# MD015A.net
KiCad netlist of a schematic drawn in Altium Designer
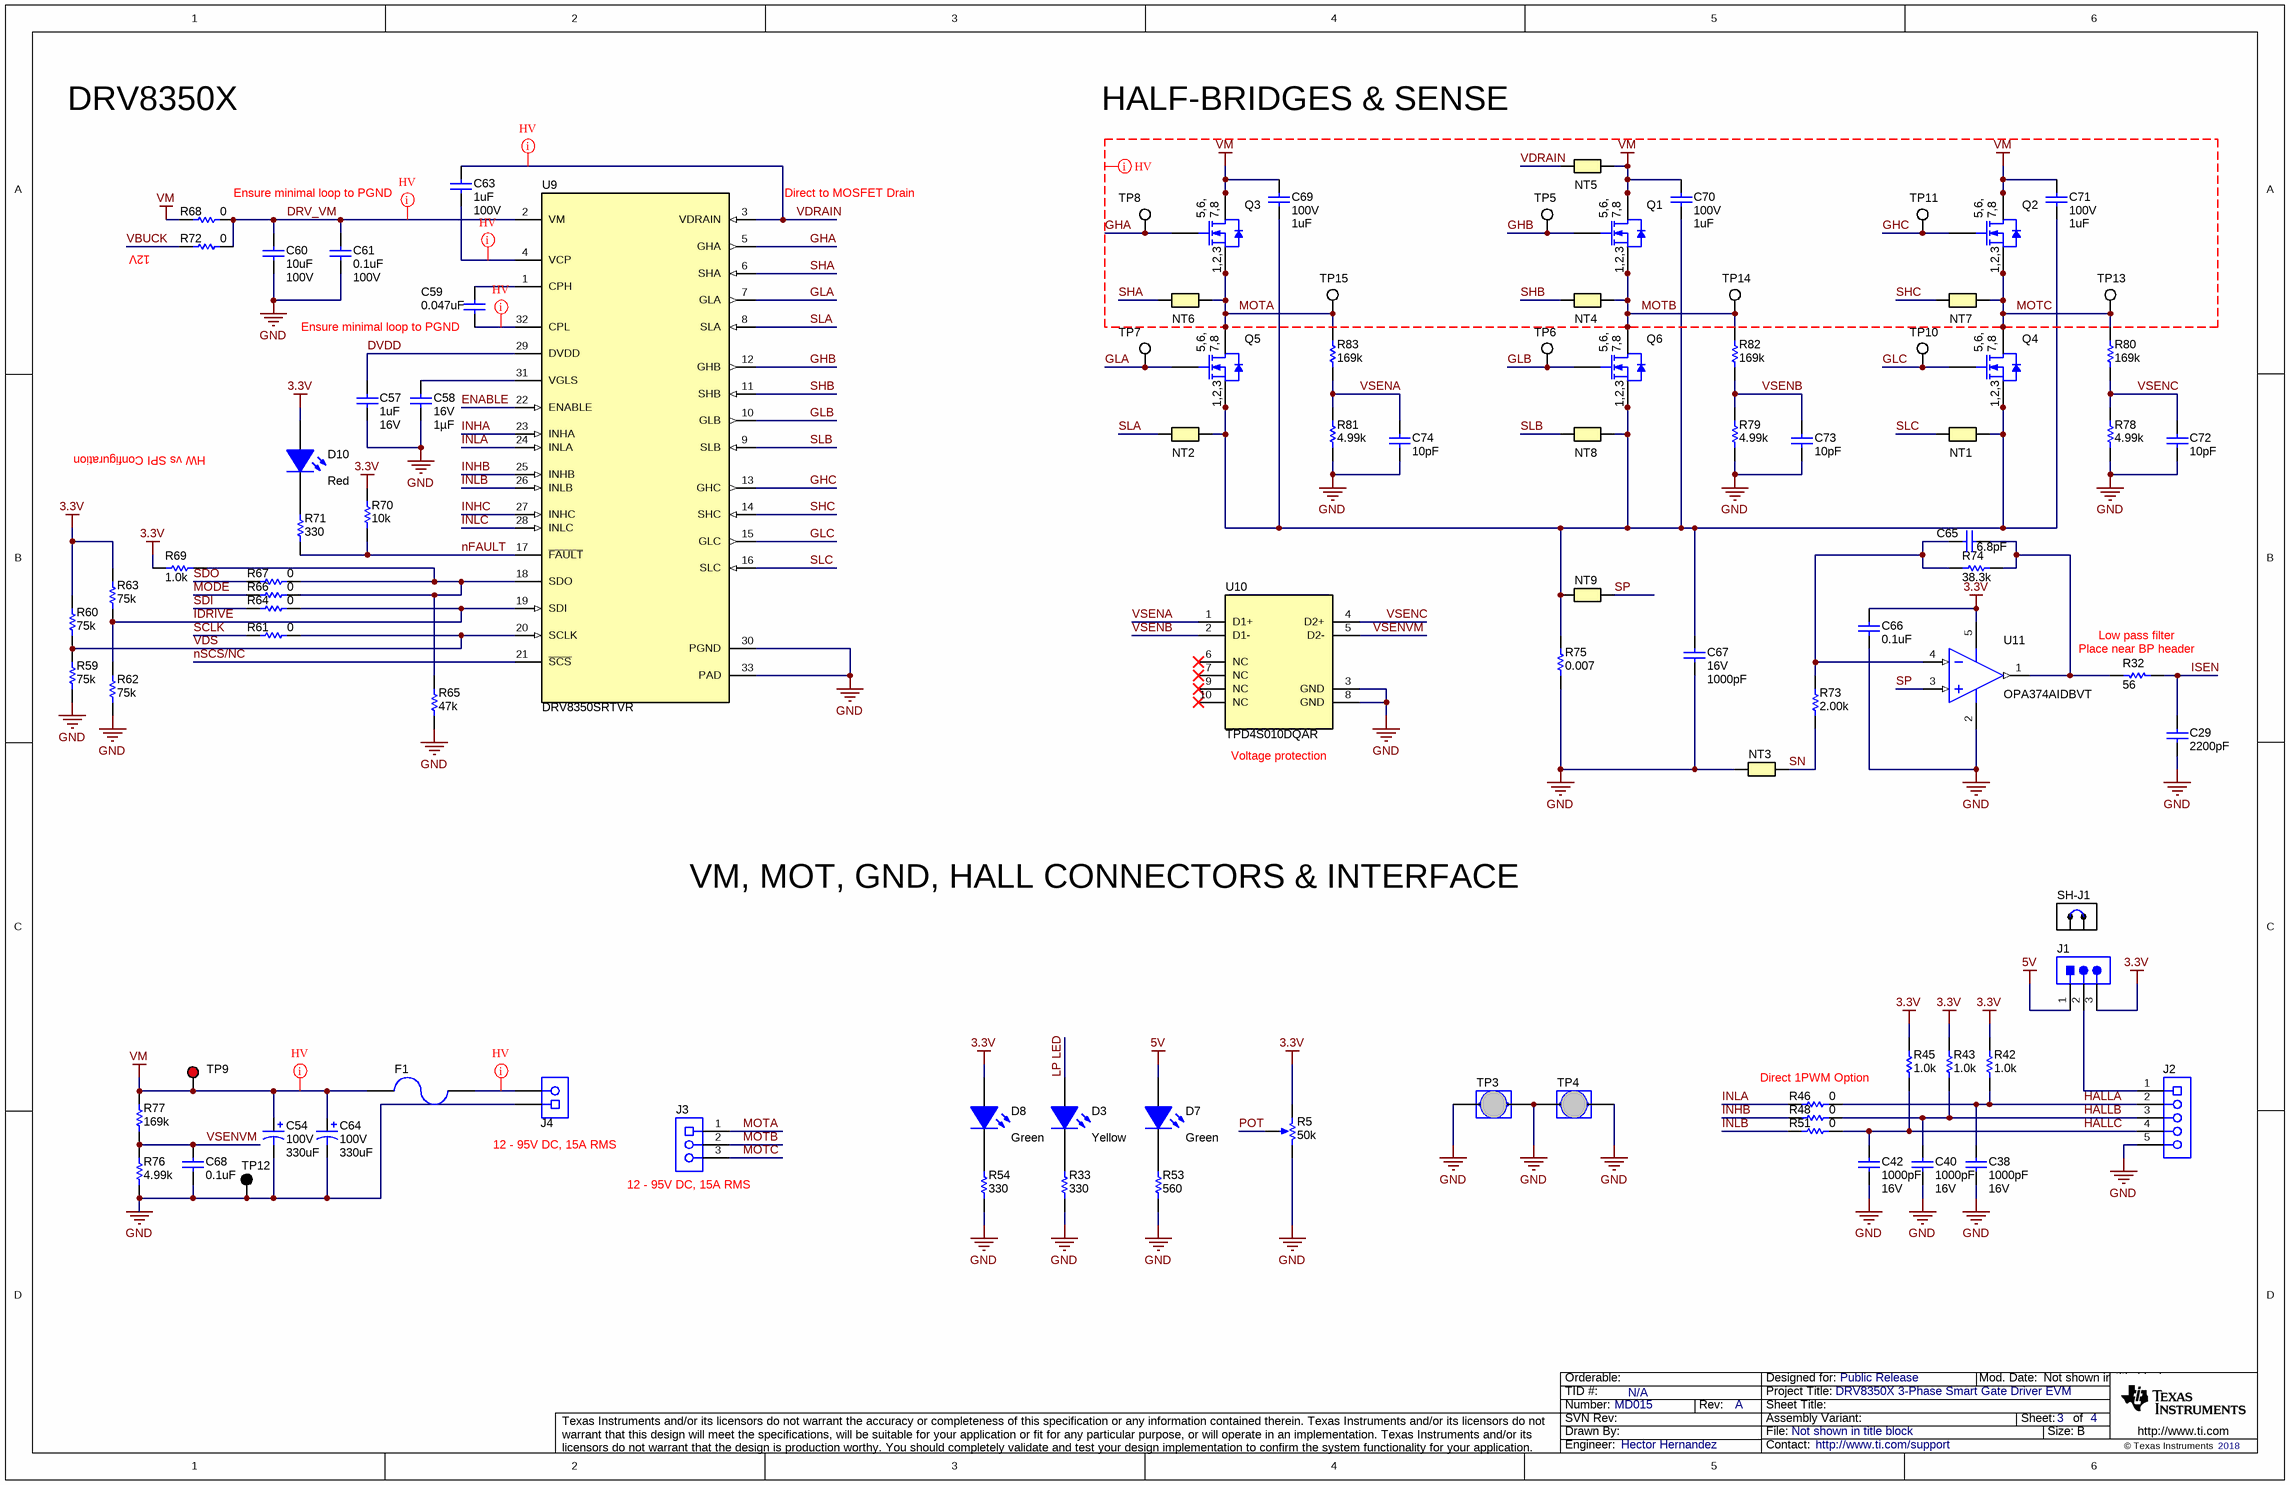
[diagram p0: MD015A.SchDoc]

(export (version "E")
  (design (tool "Eeschema 10.0.6"))
  (components
    (comp (ref "C29")
      (value "GRM188R71C222KA01D")
      (footprint "0603L")
      (description "CAP, CERM, 2200 pF, 16 V, +/- 10%, X7R, 0603")
      (fields (field (name "VALUEDISPLAYED") "2200pF") (field (name "MANUFACTURER") "MuRata"))
      (libsource (lib "Altium Vault - TI") (part "Capacitor"))
    )
    (comp (ref "C38")
      (value "885012206034")
      (footprint "0603L")
      (description "CAP, CERM, 1000 pF, 16 V, +/- 10%, X7R, 0603")
      (fields
        (field (name "MANUFACTURER") "Wurth Elektronik")
        (field (name "VALUEDISPLAYED") "1000pF")
        (field (name "VDC_V") "16V")
      )
      (libsource (lib "Altium Vault - TI") (part "Capacitor"))
    )
    (comp (ref "C40")
      (value "885012206034")
      (footprint "0603L")
      (description "CAP, CERM, 1000 pF, 16 V, +/- 10%, X7R, 0603")
      (fields
        (field (name "MANUFACTURER") "Wurth Elektronik")
        (field (name "VALUEDISPLAYED") "1000pF")
        (field (name "VDC_V") "16V")
      )
      (libsource (lib "Altium Vault - TI") (part "Capacitor"))
    )
    (comp (ref "C42")
      (value "885012206034")
      (footprint "0603L")
      (description "CAP, CERM, 1000 pF, 16 V, +/- 10%, X7R, 0603")
      (fields
        (field (name "MANUFACTURER") "Wurth Elektronik")
        (field (name "VALUEDISPLAYED") "1000pF")
        (field (name "VDC_V") "16V")
      )
      (libsource (lib "Altium Vault - TI") (part "Capacitor"))
    )
    (comp (ref "C54")
      (value "EEV-FK2A331M")
      (footprint "SM_RADIAL_K16")
      (description "CAP, AL, 330 uF, 100 V, +/- 20%, 0.153 ohm, AEC-Q200 Grade 2, SMD")
      (fields
        (field (name "MANUFACTURER") "Panasonic")
        (field (name "VDC_V") "100V")
        (field (name "VALUEDISPLAYED") "330uF")
      )
      (libsource (lib "Altium Vault - TI") (part "Cap_Polarized"))
    )
    (comp (ref "C57")
      (value "EMK107B7105KA-T")
      (footprint "0603L")
      (description "CAP, CERM, 1 uF, 16 V, +/- 10%, X7R, 0603")
      (fields
        (field (name "MANUFACTURER") "Taiyo Yuden")
        (field (name "VALUEDISPLAYED") "1uF")
        (field (name "VDC_V") "16V")
      )
      (libsource (lib "Altium Vault - TI") (part "Capacitor"))
    )
    (comp (ref "C58")
      (value "CL10B105KO8VPNC")
      (footprint "0603")
      (description "CAP, CERM, 1 µF, 16 V,+/- 10%, X7R, AEC-Q200 Grade 1, 0603")
      (fields
        (field (name "VDC_V") "16V")
        (field (name "MANUFACTURER") "Samsung Electro-Mechanics")
        (field (name "VALUEDISPLAYED") "1µF")
      )
      (libsource (lib "Altium Vault - TI") (part "Capacitor"))
    )
    (comp (ref "C59")
      (value "C2012X7R2A473K125AA")
      (footprint "0805_HV")
      (description "CAP, CERM, 0.047 uF, 100 V, +/- 10%, X7R, 0805")
      (fields (field (name "VALUEDISPLAYED") "0.047uF") (field (name "MANUFACTURER") "TDK"))
      (libsource (lib "Altium Vault - TI") (part "Capacitor"))
    )
    (comp (ref "C60")
      (value "CGA9N3X7S2A106K230KE")
      (footprint "2220_280")
      (description "CAP, CERM, 10 uF, 100 V,+/- 10%, X7S, AEC-Q200 Grade 1, 2220")
      (fields
        (field (name "MANUFACTURER") "TDK")
        (field (name "VALUEDISPLAYED") "10uF")
        (field (name "VDC_V") "100V")
      )
      (libsource (lib "Altium Vault - TI") (part "Capacitor"))
    )
    (comp (ref "C61")
      (value "C2012X7R2A104K125AA")
      (footprint "0805")
      (description "CAP, CERM, 0.1 uF, 100 V, +/- 10%, X7R, 0805")
      (fields
        (field (name "MANUFACTURER") "TDK")
        (field (name "VALUEDISPLAYED") "0.1uF")
        (field (name "VDC_V") "100V")
      )
      (libsource (lib "Altium Vault - TI") (part "Capacitor"))
    )
    (comp (ref "C63")
      (value "CL31B105KCHNNNE")
      (footprint "1206_180L")
      (description "CAP, CERM, 1 uF, 100 V, +/- 10%, X7R, 1206")
      (fields
        (field (name "MANUFACTURER") "Samsung")
        (field (name "VALUEDISPLAYED") "1uF")
        (field (name "VDC_V") "100V")
      )
      (libsource (lib "Altium Vault - TI") (part "Capacitor"))
    )
    (comp (ref "C64")
      (value "EEV-FK2A331M")
      (footprint "SM_RADIAL_K16")
      (description "CAP, AL, 330 uF, 100 V, +/- 20%, 0.153 ohm, AEC-Q200 Grade 2, SMD")
      (fields
        (field (name "MANUFACTURER") "Panasonic")
        (field (name "VDC_V") "100V")
        (field (name "VALUEDISPLAYED") "330uF")
      )
      (libsource (lib "Altium Vault - TI") (part "Cap_Polarized"))
    )
    (comp (ref "C65")
      (value "06035A6R8CAT2A")
      (footprint "0603L")
      (description "CAP, CERM, 6.8 pF, 50 V, +/- 4%, C0G/NP0, 0603")
      (fields (field (name "VALUEDISPLAYED") "6.8pF") (field (name "MANUFACTURER") "AVX"))
      (libsource (lib "Altium Vault - TI") (part "Capacitor"))
    )
    (comp (ref "C66")
      (value "C0603C104J4RACTU")
      (footprint "0603L")
      (description "CAP, CERM, 0.1 uF, 16 V, +/- 5%, X7R, 0603")
      (fields (field (name "VALUEDISPLAYED") "0.1uF") (field (name "MANUFACTURER") "Kemet"))
      (libsource (lib "Altium Vault - TI") (part "Capacitor"))
    )
    (comp (ref "C67")
      (value "885012206034")
      (footprint "0603L")
      (description "CAP, CERM, 1000 pF, 16 V, +/- 10%, X7R, 0603")
      (fields
        (field (name "MANUFACTURER") "Wurth Elektronik")
        (field (name "VDC_V") "16V")
        (field (name "VALUEDISPLAYED") "1000pF")
      )
      (libsource (lib "Altium Vault - TI") (part "Capacitor"))
    )
    (comp (ref "C68")
      (value "C0603C104J4RACTU")
      (footprint "0603L")
      (description "CAP, CERM, 0.1 uF, 16 V, +/- 5%, X7R, 0603")
      (fields (field (name "VALUEDISPLAYED") "0.1uF") (field (name "MANUFACTURER") "Kemet"))
      (libsource (lib "Altium Vault - TI") (part "Capacitor"))
    )
    (comp (ref "C69")
      (value "CL31B105KCHNNNE")
      (footprint "1206_180")
      (description "CAP, CERM, 1 uF, 100 V, +/- 10%, X7R, 1206")
      (fields
        (field (name "MANUFACTURER") "Samsung")
        (field (name "VDC_V") "100V")
        (field (name "VALUEDISPLAYED") "1uF")
      )
      (libsource (lib "Altium Vault - TI") (part "Capacitor"))
    )
    (comp (ref "C70")
      (value "CL31B105KCHNNNE")
      (footprint "1206_180")
      (description "CAP, CERM, 1 uF, 100 V, +/- 10%, X7R, 1206")
      (fields
        (field (name "MANUFACTURER") "Samsung")
        (field (name "VDC_V") "100V")
        (field (name "VALUEDISPLAYED") "1uF")
      )
      (libsource (lib "Altium Vault - TI") (part "Capacitor"))
    )
    (comp (ref "C71")
      (value "CL31B105KCHNNNE")
      (footprint "1206_180")
      (description "CAP, CERM, 1 uF, 100 V, +/- 10%, X7R, 1206")
      (fields
        (field (name "MANUFACTURER") "Samsung")
        (field (name "VDC_V") "100V")
        (field (name "VALUEDISPLAYED") "1uF")
      )
      (libsource (lib "Altium Vault - TI") (part "Capacitor"))
    )
    (comp (ref "C72")
      (value "C0603C100F5GAC7867")
      (footprint "0603L")
      (description "CAP, CERM, 10 pF, 50 V, +/- 1%, C0G/NP0, 0603")
      (fields (field (name "VALUEDISPLAYED") "10pF") (field (name "MANUFACTURER") "Kemet"))
      (libsource (lib "Altium Vault - TI") (part "Capacitor"))
    )
    (comp (ref "C73")
      (value "C0603C100F5GAC7867")
      (footprint "0603L")
      (description "CAP, CERM, 10 pF, 50 V, +/- 1%, C0G/NP0, 0603")
      (fields (field (name "VALUEDISPLAYED") "10pF") (field (name "MANUFACTURER") "Kemet"))
      (libsource (lib "Altium Vault - TI") (part "Capacitor"))
    )
    (comp (ref "C74")
      (value "C0603C100F5GAC7867")
      (footprint "0603L")
      (description "CAP, CERM, 10 pF, 50 V, +/- 1%, C0G/NP0, 0603")
      (fields (field (name "VALUEDISPLAYED") "10pF") (field (name "MANUFACTURER") "Kemet"))
      (libsource (lib "Altium Vault - TI") (part "Capacitor"))
    )
    (comp (ref "D3")
      (value "Yellow")
      (footprint "LED_LTST-C170")
      (description "LED, Yellow , SMD")
      (fields (field (name "PARTNUMBER") "LTST-C170KSKT") (field (name "MANUFACTURER") "Lite-On"))
      (libsource (lib "Altium Vault - TI") (part "LED"))
    )
    (comp (ref "D7")
      (value "Green")
      (footprint "LTST-C170KGKT_Green")
      (description "LED, Green, SMD")
      (fields (field (name "MANUFACTURER") "Lite-On") (field (name "PARTNUMBER") "LTST-C170KGKT"))
      (libsource (lib "Altium Vault - TI") (part "LED"))
    )
    (comp (ref "D8")
      (value "Green")
      (footprint "LTST-C170KGKT_Green")
      (description "LED, Green, SMD")
      (fields (field (name "MANUFACTURER") "Lite-On") (field (name "PARTNUMBER") "LTST-C170KGKT"))
      (libsource (lib "Altium Vault - TI") (part "LED"))
    )
    (comp (ref "D10")
      (value "Red")
      (footprint "LED_LTST-C170_Red")
      (description "LED, Red, SMD")
      (fields (field (name "MANUFACTURER") "Lite-On") (field (name "PARTNUMBER") "LTST-C170KRKT"))
      (libsource (lib "Altium Vault - TI") (part "LED"))
    )
    (comp (ref "F1")
      (value "0463030.ER")
      (footprint "Fuse_0463")
      (description "Fuse, 30 A, 250 VAC, 100 VDC, SMD")
      (fields (field (name "MANUFACTURER") "Littelfuse"))
      (libsource (lib "Altium Vault - TI") (part "Fuse"))
    )
    (comp (ref "J1")
      (value "22284030")
      (footprint "Molex_0022284030")
      (description "Header, 2.54mm, 3x1, Tin, TH")
      (fields (field (name "MANUFACTURER") "Molex"))
      (libsource (lib "Altium Vault - TI") (part "Header_3x1"))
    )
    (comp (ref "J2")
      (value "1792892")
      (footprint "Phoenix_1792892")
      (description "Terminal Block, 5mm, 5x1, R/A, TH")
      (fields (field (name "MANUFACTURER") "Phoenix Contact"))
      (libsource (lib "Altium Vault - TI") (part "Receptacle_5x1"))
    )
    (comp (ref "J3")
      (value "1904150")
      (footprint "Phoenix_1904150")
      (description "Terminal Block, 9.52mm, 3x1, R/A, TH")
      (fields (field (name "MANUFACTURER") "Phoenix Contact"))
      (libsource (lib "Altium Vault - TI") (part "Receptacle_3x1"))
    )
    (comp (ref "J4")
      (value "1902547")
      (footprint "Phoenix_1902547")
      (description "Terminal Block, 9.52mm, 2x1, R/A, TH")
      (fields (field (name "MANUFACTURER") "Phoenix Contact"))
      (libsource (lib "Altium Vault - TI") (part "Receptacle_2x1"))
    )
    (comp (ref "NT1")
      (value "Net-Tie")
      (footprint "Net-Tie_20milWide_60milLong")
      (description "Single point connection between nets.")
      (libsource (lib "Altium Vault - TI") (part "Net-Tie"))
    )
    (comp (ref "NT2")
      (value "Net-Tie")
      (footprint "Net-Tie_20milWide_60milLong")
      (description "Single point connection between nets.")
      (libsource (lib "Altium Vault - TI") (part "Net-Tie"))
    )
    (comp (ref "NT3")
      (value "Net-Tie")
      (footprint "Net-Tie_20milWide_60milLong")
      (description "Single point connection between nets.")
      (libsource (lib "Altium Vault - TI") (part "Net-Tie"))
    )
    (comp (ref "NT4")
      (value "Net-Tie")
      (footprint "Net-Tie_20milWide_60milLong")
      (description "Single point connection between nets.")
      (libsource (lib "Altium Vault - TI") (part "Net-Tie"))
    )
    (comp (ref "NT5")
      (value "Net-Tie")
      (footprint "Net-Tie_50milWide_30milLong")
      (description "Single point connection between nets.")
      (libsource (lib "Altium Vault - TI") (part "Net-Tie"))
    )
    (comp (ref "NT6")
      (value "Net-Tie")
      (footprint "Net-Tie_20milWide_60milLong")
      (description "Single point connection between nets.")
      (libsource (lib "Altium Vault - TI") (part "Net-Tie"))
    )
    (comp (ref "NT7")
      (value "Net-Tie")
      (footprint "Net-Tie_20milWide_60milLong")
      (description "Single point connection between nets.")
      (libsource (lib "Altium Vault - TI") (part "Net-Tie"))
    )
    (comp (ref "NT8")
      (value "Net-Tie")
      (footprint "Net-Tie_20milWide_60milLong")
      (description "Single point connection between nets.")
      (libsource (lib "Altium Vault - TI") (part "Net-Tie"))
    )
    (comp (ref "NT9")
      (value "Net-Tie")
      (footprint "Net-Tie_20milWide_60milLong")
      (description "Single point connection between nets.")
      (libsource (lib "Altium Vault - TI") (part "Net-Tie"))
    )
    (comp (ref "Q1")
      (value "CSD19532Q5B")
      (footprint "DNK0008A")
      (description "MOSFET, N-CH, 100 V, 17 A, DNK0008A (VSON-CLIP-8)")
      (fields (field (name "MANUFACTURER") "Texas Instruments"))
      (libsource (lib "Altium Vault - TI") (part "MOSFET_N_D56789G4S123"))
    )
    (comp (ref "Q2")
      (value "CSD19532Q5B")
      (footprint "DNK0008A")
      (description "MOSFET, N-CH, 100 V, 17 A, DNK0008A (VSON-CLIP-8)")
      (fields (field (name "MANUFACTURER") "Texas Instruments"))
      (libsource (lib "Altium Vault - TI") (part "MOSFET_N_D56789G4S123"))
    )
    (comp (ref "Q3")
      (value "CSD19532Q5B")
      (footprint "DNK0008A")
      (description "MOSFET, N-CH, 100 V, 17 A, DNK0008A (VSON-CLIP-8)")
      (fields (field (name "MANUFACTURER") "Texas Instruments"))
      (libsource (lib "Altium Vault - TI") (part "MOSFET_N_D56789G4S123"))
    )
    (comp (ref "Q4")
      (value "CSD19532Q5B")
      (footprint "DNK0008A")
      (description "MOSFET, N-CH, 100 V, 17 A, DNK0008A (VSON-CLIP-8)")
      (fields (field (name "MANUFACTURER") "Texas Instruments"))
      (libsource (lib "Altium Vault - TI") (part "MOSFET_N_D56789G4S123"))
    )
    (comp (ref "Q5")
      (value "CSD19532Q5B")
      (footprint "DNK0008A")
      (description "MOSFET, N-CH, 100 V, 17 A, DNK0008A (VSON-CLIP-8)")
      (fields (field (name "MANUFACTURER") "Texas Instruments"))
      (libsource (lib "Altium Vault - TI") (part "MOSFET_N_D56789G4S123"))
    )
    (comp (ref "Q6")
      (value "CSD19532Q5B")
      (footprint "DNK0008A")
      (description "MOSFET, N-CH, 100 V, 17 A, DNK0008A (VSON-CLIP-8)")
      (fields (field (name "MANUFACTURER") "Texas Instruments"))
      (libsource (lib "Altium Vault - TI") (part "MOSFET_N_D56789G4S123"))
    )
    (comp (ref "R5")
      (value "50k")
      (footprint "Bourns_3352T")
      (description "Trimming Potentiometer, 50K, 0.5W, TH")
      (fields (field (name "PARTNUMBER") "3352T-1-503LF") (field (name "MANUFACTURER") "Bourns"))
      (libsource (lib "Altium Vault - TI") (part "Potentiometer"))
    )
    (comp (ref "R32")
      (value "56")
      (footprint "0603L")
      (description "RES, 56, 5%, 0.1 W, AEC-Q200 Grade 0, 0603")
      (fields (field (name "PARTNUMBER") "CRCW060356R0JNEA") (field (name "MANUFACTURER") "Vishay-Dale"))
      (libsource (lib "Altium Vault - TI") (part "Resistor"))
    )
    (comp (ref "R33")
      (value "CRCW0603330RJNEA")
      (footprint "0603L")
      (description "RES, 330, 5%, 0.1 W, AEC-Q200 Grade 0, 0603")
      (fields (field (name "MANUFACTURER") "Vishay-Dale") (field (name "VALUEDISPLAYED") "330"))
      (libsource (lib "Altium Vault - TI") (part "Resistor"))
    )
    (comp (ref "R42")
      (value "RCA06031K00JNEA")
      (footprint "0603L")
      (description "RES, 1.0 k, 5%, 0.1 W, AEC-Q200 Grade 0, 0603")
      (fields (field (name "MANUFACTURER") "Vishay-Dale") (field (name "VALUEDISPLAYED") "1.0k"))
      (libsource (lib "Altium Vault - TI") (part "Resistor"))
    )
    (comp (ref "R43")
      (value "RCA06031K00JNEA")
      (footprint "0603L")
      (description "RES, 1.0 k, 5%, 0.1 W, AEC-Q200 Grade 0, 0603")
      (fields (field (name "MANUFACTURER") "Vishay-Dale") (field (name "VALUEDISPLAYED") "1.0k"))
      (libsource (lib "Altium Vault - TI") (part "Resistor"))
    )
    (comp (ref "R45")
      (value "RCA06031K00JNEA")
      (footprint "0603L")
      (description "RES, 1.0 k, 5%, 0.1 W, AEC-Q200 Grade 0, 0603")
      (fields (field (name "MANUFACTURER") "Vishay-Dale") (field (name "VALUEDISPLAYED") "1.0k"))
      (libsource (lib "Altium Vault - TI") (part "Resistor"))
    )
    (comp (ref "R46")
      (value "CRCW06030000Z0EA")
      (footprint "0603L")
      (description "RES, 0, 5%, 0.1 W, AEC-Q200 Grade 0, 0603")
      (fields (field (name "MANUFACTURER") "Vishay-Dale") (field (name "VALUEDISPLAYED") "0"))
      (libsource (lib "Altium Vault - TI") (part "Resistor"))
    )
    (comp (ref "R48")
      (value "CRCW06030000Z0EA")
      (footprint "0603L")
      (description "RES, 0, 5%, 0.1 W, AEC-Q200 Grade 0, 0603")
      (fields (field (name "MANUFACTURER") "Vishay-Dale") (field (name "VALUEDISPLAYED") "0"))
      (libsource (lib "Altium Vault - TI") (part "Resistor"))
    )
    (comp (ref "R51")
      (value "CRCW06030000Z0EA")
      (footprint "0603L")
      (description "RES, 0, 5%, 0.1 W, AEC-Q200 Grade 0, 0603")
      (fields (field (name "MANUFACTURER") "Vishay-Dale") (field (name "VALUEDISPLAYED") "0"))
      (libsource (lib "Altium Vault - TI") (part "Resistor"))
    )
    (comp (ref "R53")
      (value "RG1608P-561-B-T5")
      (footprint "0603L")
      (description "RES, 560, 0.1%, 0.1 W, 0603")
      (fields (field (name "MANUFACTURER") "Susumu Co Ltd") (field (name "VALUEDISPLAYED") "560"))
      (libsource (lib "Altium Vault - TI") (part "Resistor"))
    )
    (comp (ref "R54")
      (value "CRCW0603330RJNEA")
      (footprint "0603L")
      (description "RES, 330, 5%, 0.1 W, AEC-Q200 Grade 0, 0603")
      (fields (field (name "MANUFACTURER") "Vishay-Dale") (field (name "VALUEDISPLAYED") "330"))
      (libsource (lib "Altium Vault - TI") (part "Resistor"))
    )
    (comp (ref "R59")
      (value "CRCW060375K0JNEA")
      (footprint "0603L")
      (description "RES, 75 k, 5%, 0.1 W, AEC-Q200 Grade 0, 0603")
      (fields (field (name "VALUEDISPLAYED") "75k") (field (name "MANUFACTURER") "Vishay-Dale"))
      (libsource (lib "Altium Vault - TI") (part "Resistor"))
    )
    (comp (ref "R60")
      (value "CRCW060375K0JNEA")
      (footprint "0603L")
      (description "RES, 75 k, 5%, 0.1 W, AEC-Q200 Grade 0, 0603")
      (fields (field (name "VALUEDISPLAYED") "75k") (field (name "MANUFACTURER") "Vishay-Dale"))
      (libsource (lib "Altium Vault - TI") (part "Resistor"))
    )
    (comp (ref "R61")
      (value "CRCW06030000Z0EA")
      (footprint "0603L")
      (description "RES, 0, 5%, 0.1 W, AEC-Q200 Grade 0, 0603")
      (fields (field (name "MANUFACTURER") "Vishay-Dale") (field (name "VALUEDISPLAYED") "0"))
      (libsource (lib "Altium Vault - TI") (part "Resistor"))
    )
    (comp (ref "R62")
      (value "CRCW060375K0JNEA")
      (footprint "0603L")
      (description "RES, 75 k, 5%, 0.1 W, AEC-Q200 Grade 0, 0603")
      (fields (field (name "VALUEDISPLAYED") "75k") (field (name "MANUFACTURER") "Vishay-Dale"))
      (libsource (lib "Altium Vault - TI") (part "Resistor"))
    )
    (comp (ref "R63")
      (value "CRCW060375K0JNEA")
      (footprint "0603L")
      (description "RES, 75 k, 5%, 0.1 W, AEC-Q200 Grade 0, 0603")
      (fields (field (name "VALUEDISPLAYED") "75k") (field (name "MANUFACTURER") "Vishay-Dale"))
      (libsource (lib "Altium Vault - TI") (part "Resistor"))
    )
    (comp (ref "R64")
      (value "CRCW06030000Z0EA")
      (footprint "0603L")
      (description "RES, 0, 5%, 0.1 W, AEC-Q200 Grade 0, 0603")
      (fields (field (name "MANUFACTURER") "Vishay-Dale") (field (name "VALUEDISPLAYED") "0"))
      (libsource (lib "Altium Vault - TI") (part "Resistor"))
    )
    (comp (ref "R65")
      (value "CRCW060347K0JNEA")
      (footprint "0603L")
      (description "RES, 47 k, 5%, 0.1 W, AEC-Q200 Grade 0, 0603")
      (fields (field (name "VALUEDISPLAYED") "47k") (field (name "MANUFACTURER") "Vishay-Dale"))
      (libsource (lib "Altium Vault - TI") (part "Resistor"))
    )
    (comp (ref "R66")
      (value "CRCW06030000Z0EA")
      (footprint "0603L")
      (description "RES, 0, 5%, 0.1 W, AEC-Q200 Grade 0, 0603")
      (fields (field (name "MANUFACTURER") "Vishay-Dale") (field (name "VALUEDISPLAYED") "0"))
      (libsource (lib "Altium Vault - TI") (part "Resistor"))
    )
    (comp (ref "R67")
      (value "CRCW06030000Z0EA")
      (footprint "0603L")
      (description "RES, 0, 5%, 0.1 W, AEC-Q200 Grade 0, 0603")
      (fields (field (name "MANUFACTURER") "Vishay-Dale") (field (name "VALUEDISPLAYED") "0"))
      (libsource (lib "Altium Vault - TI") (part "Resistor"))
    )
    (comp (ref "R68")
      (value "RC1206JR-070RL")
      (footprint "1206")
      (description "RES, 0, 5%, 0.25 W, 1206")
      (fields (field (name "MANUFACTURER") "Yageo America") (field (name "VALUEDISPLAYED") "0"))
      (libsource (lib "Altium Vault - TI") (part "Resistor"))
    )
    (comp (ref "R69")
      (value "RCA06031K00JNEA")
      (footprint "0603L")
      (description "RES, 1.0 k, 5%, 0.1 W, AEC-Q200 Grade 0, 0603")
      (fields (field (name "MANUFACTURER") "Vishay-Dale") (field (name "VALUEDISPLAYED") "1.0k"))
      (libsource (lib "Altium Vault - TI") (part "Resistor"))
    )
    (comp (ref "R70")
      (value "RC0603JR-0710KL")
      (footprint "0603L")
      (description "RES, 10 k, 5%, 0.1 W, 0603")
      (fields (field (name "MANUFACTURER") "Yageo") (field (name "VALUEDISPLAYED") "10k"))
      (libsource (lib "Altium Vault - TI") (part "Resistor"))
    )
    (comp (ref "R71")
      (value "CRCW0603330RJNEA")
      (footprint "0603L")
      (description "RES, 330, 5%, 0.1 W, AEC-Q200 Grade 0, 0603")
      (fields (field (name "MANUFACTURER") "Vishay-Dale") (field (name "VALUEDISPLAYED") "330"))
      (libsource (lib "Altium Vault - TI") (part "Resistor"))
    )
    (comp (ref "R72")
      (value "RC1206JR-070RL")
      (footprint "1206")
      (description "RES, 0, 5%, 0.25 W, 1206")
      (fields (field (name "MANUFACTURER") "Yageo America") (field (name "VALUEDISPLAYED") "0"))
      (libsource (lib "Altium Vault - TI") (part "Resistor"))
    )
    (comp (ref "R73")
      (value "RC0603FR-072KL")
      (footprint "0603L")
      (description "RES, 2.00 k, 1%, 0.1 W, 0603")
      (fields (field (name "MANUFACTURER") "Yageo") (field (name "VALUEDISPLAYED") "2.00k"))
      (libsource (lib "Altium Vault - TI") (part "Resistor"))
    )
    (comp (ref "R74")
      (value "CRCW060338K3FKEA")
      (footprint "0603L")
      (description "RES, 38.3 k, 1%, 0.1 W, AEC-Q200 Grade 0, 0603")
      (fields (field (name "VALUEDISPLAYED") "38.3k") (field (name "MANUFACTURER") "Vishay-Dale"))
      (libsource (lib "Altium Vault - TI") (part "Resistor"))
    )
    (comp (ref "R75")
      (value "CRE2512-FZ-R007E-3")
      (footprint "CRE2512-R5_R9")
      (description "RES, 0.007, 1%, 3 W, AEC-Q200 Grade 0, 2512")
      (fields (field (name "VALUEDISPLAYED") "0.007") (field (name "MANUFACTURER") "Bourns"))
      (libsource (lib "Altium Vault - TI") (part "Resistor"))
    )
    (comp (ref "R76")
      (value "RC0603FR-074K99L")
      (footprint "0603L")
      (description "RES, 4.99 k, 1%, 0.1 W, 0603")
      (fields (field (name "VALUEDISPLAYED") "4.99k") (field (name "MANUFACTURER") "Yageo"))
      (libsource (lib "Altium Vault - TI") (part "Resistor"))
    )
    (comp (ref "R77")
      (value "RC0603FR-07169KL")
      (footprint "0603_HV")
      (description "RES, 169 k, 1%, 0.1 W, 0603")
      (fields (field (name "VALUEDISPLAYED") "169k") (field (name "MANUFACTURER") "Yageo"))
      (libsource (lib "Altium Vault - TI") (part "Resistor"))
    )
    (comp (ref "R78")
      (value "RC0603FR-074K99L")
      (footprint "0603L")
      (description "RES, 4.99 k, 1%, 0.1 W, 0603")
      (fields (field (name "VALUEDISPLAYED") "4.99k") (field (name "MANUFACTURER") "Yageo"))
      (libsource (lib "Altium Vault - TI") (part "Resistor"))
    )
    (comp (ref "R79")
      (value "RC0603FR-074K99L")
      (footprint "0603L")
      (description "RES, 4.99 k, 1%, 0.1 W, 0603")
      (fields (field (name "VALUEDISPLAYED") "4.99k") (field (name "MANUFACTURER") "Yageo"))
      (libsource (lib "Altium Vault - TI") (part "Resistor"))
    )
    (comp (ref "R80")
      (value "RC0603FR-07169KL")
      (footprint "0603_HV")
      (description "RES, 169 k, 1%, 0.1 W, 0603")
      (fields (field (name "VALUEDISPLAYED") "169k") (field (name "MANUFACTURER") "Yageo"))
      (libsource (lib "Altium Vault - TI") (part "Resistor"))
    )
    (comp (ref "R81")
      (value "RC0603FR-074K99L")
      (footprint "0603L")
      (description "RES, 4.99 k, 1%, 0.1 W, 0603")
      (fields (field (name "VALUEDISPLAYED") "4.99k") (field (name "MANUFACTURER") "Yageo"))
      (libsource (lib "Altium Vault - TI") (part "Resistor"))
    )
    (comp (ref "R82")
      (value "RC0603FR-07169KL")
      (footprint "0603_HV")
      (description "RES, 169 k, 1%, 0.1 W, 0603")
      (fields (field (name "VALUEDISPLAYED") "169k") (field (name "MANUFACTURER") "Yageo"))
      (libsource (lib "Altium Vault - TI") (part "Resistor"))
    )
    (comp (ref "R83")
      (value "RC0603FR-07169KL")
      (footprint "0603_HV")
      (description "RES, 169 k, 1%, 0.1 W, 0603")
      (fields (field (name "VALUEDISPLAYED") "169k") (field (name "MANUFACTURER") "Yageo"))
      (libsource (lib "Altium Vault - TI") (part "Resistor"))
    )
    (comp (ref "SH-J1")
      (value "SNT-100-BK-G")
      (footprint "SNT-100-BK-G")
      (description "Shunt, 100mil, Gold plated, Black")
      (fields (field (name "ALTERNATE PARTNUMBER") "969102-0000-DA") (field (name "MANUFACTURER") "Samtec"))
      (libsource (lib "Altium Vault - TI") (part "Shunt"))
    )
    (comp (ref "TP3")
      (value "D3082-05")
      (footprint "Harwin_D3082-05")
      (description "1mm Uninsulated Shorting Plug, 10.16mm spacing, TH")
      (fields (field (name "MANUFACTURER") "Harwin"))
      (libsource (lib "Altium Vault - TI") (part "Jumper_2p"))
    )
    (comp (ref "TP4")
      (value "D3082-05")
      (footprint "Harwin_D3082-05")
      (description "1mm Uninsulated Shorting Plug, 10.16mm spacing, TH")
      (fields (field (name "MANUFACTURER") "Harwin"))
      (libsource (lib "Altium Vault - TI") (part "Jumper_2p"))
    )
    (comp (ref "TP5")
      (value "5002")
      (footprint "Keystone5002")
      (description "Test Point, Miniature, White, TH")
      (fields (field (name "MANUFACTURER") "Keystone"))
      (libsource (lib "Altium Vault - TI") (part "5002"))
    )
    (comp (ref "TP6")
      (value "5002")
      (footprint "Keystone5002")
      (description "Test Point, Miniature, White, TH")
      (fields (field (name "MANUFACTURER") "Keystone"))
      (libsource (lib "Altium Vault - TI") (part "5002"))
    )
    (comp (ref "TP7")
      (value "5002")
      (footprint "Keystone5002")
      (description "Test Point, Miniature, White, TH")
      (fields (field (name "MANUFACTURER") "Keystone"))
      (libsource (lib "Altium Vault - TI") (part "5002"))
    )
    (comp (ref "TP8")
      (value "5002")
      (footprint "Keystone5002")
      (description "Test Point, Miniature, White, TH")
      (fields (field (name "MANUFACTURER") "Keystone"))
      (libsource (lib "Altium Vault - TI") (part "5002"))
    )
    (comp (ref "TP9")
      (value "5000")
      (footprint "Keystone5000")
      (description "Test Point, Miniature, Red, TH")
      (fields (field (name "MANUFACTURER") "Keystone"))
      (libsource (lib "Altium Vault - TI") (part "5000"))
    )
    (comp (ref "TP10")
      (value "5002")
      (footprint "Keystone5002")
      (description "Test Point, Miniature, White, TH")
      (fields (field (name "MANUFACTURER") "Keystone"))
      (libsource (lib "Altium Vault - TI") (part "5002"))
    )
    (comp (ref "TP11")
      (value "5002")
      (footprint "Keystone5002")
      (description "Test Point, Miniature, White, TH")
      (fields (field (name "MANUFACTURER") "Keystone"))
      (libsource (lib "Altium Vault - TI") (part "5002"))
    )
    (comp (ref "TP12")
      (value "5001")
      (footprint "Keystone5001")
      (description "Test Point, Miniature, Black, TH")
      (fields (field (name "MANUFACTURER") "Keystone"))
      (libsource (lib "Altium Vault - TI") (part "5001"))
    )
    (comp (ref "TP13")
      (value "5002")
      (footprint "Keystone5002")
      (description "Test Point, Miniature, White, TH")
      (fields (field (name "MANUFACTURER") "Keystone"))
      (libsource (lib "Altium Vault - TI") (part "5002"))
    )
    (comp (ref "TP14")
      (value "5002")
      (footprint "Keystone5002")
      (description "Test Point, Miniature, White, TH")
      (fields (field (name "MANUFACTURER") "Keystone"))
      (libsource (lib "Altium Vault - TI") (part "5002"))
    )
    (comp (ref "TP15")
      (value "5002")
      (footprint "Keystone5002")
      (description "Test Point, Miniature, White, TH")
      (fields (field (name "MANUFACTURER") "Keystone"))
      (libsource (lib "Altium Vault - TI") (part "5002"))
    )
    (comp (ref "U9")
      (value "DRV8350SRTVR")
      (footprint "RTV0032E")
      (description "100-V Three-Phase Smart Gate Driver, RTV0032E (WQFN-32)")
      (fields
        (field (name "PARTNUMBER") "DRV8350SRTVR")
        (field (name "MANUFACTURER") "Texas Instruments")
        (field (name "ALTERNATE PARTNUMBER") "DRV8350SRTVT")
      )
      (libsource (lib "Altium Vault - TI") (part "DRV8350S"))
    )
    (comp (ref "U10")
      (value "TPD4S010DQAR")
      (footprint "DQA0010A")
      (fields (field (name "MANUFACTURER") "Texas Instruments") (field (name "PARTNUMBER") "TPD4S010DQAR"))
      (libsource (lib "Altium Vault - TI") (part "TI-TPD4S010-SON_DQA-10"))
    )
    (comp (ref "U11")
      (value "OPA374AIDBVT")
      (footprint "DBV0005A_L")
      (fields (field (name "MANUFACTURER") "Texas Instruments"))
      (libsource (lib "Altium Vault - TI") (part "TI-OPA_SM7XXXX-DBV5"))
    )
  )
  (nets
    (net (code "1") (name "/DRV_VM") (class "Default")
      (node (ref "C60") (pin "1") (pinfunction "1_1") (pintype "passive"))
      (node (ref "C61") (pin "1") (pinfunction "1_1") (pintype "passive"))
      (node (ref "R68") (pin "2") (pinfunction "2_2") (pintype "passive"))
      (node (ref "R72") (pin "2") (pinfunction "2_2") (pintype "passive"))
      (node (ref "U9") (pin "2") (pinfunction "VM_2") (pintype "power_in"))
    )
    (net (code "2") (name "/DVDD") (class "Default")
      (node (ref "C57") (pin "1") (pinfunction "1_1") (pintype "passive"))
      (node (ref "U9") (pin "29") (pinfunction "DVDD_29") (pintype "power_in"))
    )
    (net (code "3") (name "/ENABLE") (class "Default")
      (node (ref "U9") (pin "22") (pinfunction "ENABLE_22") (pintype "input"))
    )
    (net (code "4") (name "/GHA") (class "Default")
      (node (ref "Q3") (pin "4") (pinfunction "G_4") (pintype "passive"))
      (node (ref "TP8") (pin "1") (pintype "passive"))
      (node (ref "U9") (pin "5") (pinfunction "GHA_5") (pintype "output"))
    )
    (net (code "5") (name "/GHB") (class "Default")
      (node (ref "Q1") (pin "4") (pinfunction "G_4") (pintype "passive"))
      (node (ref "TP5") (pin "1") (pintype "passive"))
      (node (ref "U9") (pin "12") (pinfunction "GHB_12") (pintype "output"))
    )
    (net (code "6") (name "/GHC") (class "Default")
      (node (ref "Q2") (pin "4") (pinfunction "G_4") (pintype "passive"))
      (node (ref "TP11") (pin "1") (pintype "passive"))
      (node (ref "U9") (pin "13") (pinfunction "GHC_13") (pintype "output"))
    )
    (net (code "7") (name "/GLA") (class "Default")
      (node (ref "Q5") (pin "4") (pinfunction "G_4") (pintype "passive"))
      (node (ref "TP7") (pin "1") (pintype "passive"))
      (node (ref "U9") (pin "7") (pinfunction "GLA_7") (pintype "output"))
    )
    (net (code "8") (name "/GLB") (class "Default")
      (node (ref "Q6") (pin "4") (pinfunction "G_4") (pintype "passive"))
      (node (ref "TP6") (pin "1") (pintype "passive"))
      (node (ref "U9") (pin "10") (pinfunction "GLB_10") (pintype "output"))
    )
    (net (code "9") (name "/GLC") (class "Default")
      (node (ref "Q4") (pin "4") (pinfunction "G_4") (pintype "passive"))
      (node (ref "TP10") (pin "1") (pintype "passive"))
      (node (ref "U9") (pin "15") (pinfunction "GLC_15") (pintype "output"))
    )
    (net (code "10") (name "/HALLA") (class "Default")
      (node (ref "C38") (pin "1") (pinfunction "1_1") (pintype "passive"))
      (node (ref "J2") (pin "2") (pinfunction "2_2") (pintype "passive"))
      (node (ref "R42") (pin "1") (pinfunction "1_1") (pintype "passive"))
      (node (ref "R46") (pin "2") (pinfunction "2_2") (pintype "passive"))
    )
    (net (code "11") (name "/HALLB") (class "Default")
      (node (ref "C40") (pin "1") (pinfunction "1_1") (pintype "passive"))
      (node (ref "J2") (pin "3") (pinfunction "3_3") (pintype "passive"))
      (node (ref "R43") (pin "1") (pinfunction "1_1") (pintype "passive"))
      (node (ref "R48") (pin "2") (pinfunction "2_2") (pintype "passive"))
    )
    (net (code "12") (name "/HALLC") (class "Default")
      (node (ref "C42") (pin "1") (pinfunction "1_1") (pintype "passive"))
      (node (ref "J2") (pin "4") (pinfunction "4_4") (pintype "passive"))
      (node (ref "R45") (pin "1") (pinfunction "1_1") (pintype "passive"))
      (node (ref "R51") (pin "2") (pinfunction "2_2") (pintype "passive"))
    )
    (net (code "13") (name "/IDRIVE") (class "Default")
      (node (ref "R62") (pin "2") (pinfunction "2_2") (pintype "passive"))
      (node (ref "R63") (pin "1") (pinfunction "1_1") (pintype "passive"))
      (node (ref "R64") (pin "2") (pinfunction "2_2") (pintype "passive"))
      (node (ref "U9") (pin "19") (pinfunction "SDI_19") (pintype "input"))
    )
    (net (code "14") (name "/INHA") (class "Default")
      (node (ref "U9") (pin "23") (pinfunction "INHA_23") (pintype "input"))
    )
    (net (code "15") (name "/INHB") (class "Default")
      (node (ref "R48") (pin "1") (pinfunction "1_1") (pintype "passive"))
      (node (ref "U9") (pin "25") (pinfunction "INHB_25") (pintype "input"))
    )
    (net (code "16") (name "/INHC") (class "Default")
      (node (ref "U9") (pin "27") (pinfunction "INHC_27") (pintype "input"))
    )
    (net (code "17") (name "/INLA") (class "Default")
      (node (ref "R46") (pin "1") (pinfunction "1_1") (pintype "passive"))
      (node (ref "U9") (pin "24") (pinfunction "INLA_24") (pintype "input"))
    )
    (net (code "18") (name "/INLB") (class "Default")
      (node (ref "R51") (pin "1") (pinfunction "1_1") (pintype "passive"))
      (node (ref "U9") (pin "26") (pinfunction "INLB_26") (pintype "input"))
    )
    (net (code "19") (name "/INLC") (class "Default")
      (node (ref "U9") (pin "28") (pinfunction "INLC_28") (pintype "input"))
    )
    (net (code "20") (name "/ISEN") (class "Default")
      (node (ref "C29") (pin "1") (pinfunction "1_1") (pintype "passive"))
      (node (ref "R32") (pin "1") (pinfunction "1_1") (pintype "passive"))
    )
    (net (code "21") (name "/LP LED") (class "Default")
      (node (ref "D3") (pin "1") (pinfunction "A_1") (pintype "passive"))
    )
    (net (code "22") (name "/MODE") (class "Default")
      (node (ref "R66") (pin "1") (pinfunction "1_1") (pintype "passive"))
    )
    (net (code "23") (name "/MOTA") (class "Default")
      (node (ref "J3") (pin "1") (pinfunction "1_1") (pintype "passive"))
      (node (ref "NT6") (pin "2") (pinfunction "2_2") (pintype "passive"))
      (node (ref "Q3") (pin "1") (pinfunction "S_1") (pintype "passive"))
      (node (ref "Q3") (pin "2") (pinfunction "S_2") (pintype "passive"))
      (node (ref "Q3") (pin "3") (pinfunction "S_3") (pintype "passive"))
      (node (ref "Q5") (pin "5") (pinfunction "D_5") (pintype "passive"))
      (node (ref "Q5") (pin "6") (pinfunction "D_6") (pintype "passive"))
      (node (ref "Q5") (pin "7") (pinfunction "D_7") (pintype "passive"))
      (node (ref "Q5") (pin "8") (pinfunction "D_8") (pintype "passive"))
      (node (ref "Q5") (pin "9") (pinfunction "D_9") (pintype "passive"))
      (node (ref "R83") (pin "2") (pinfunction "2_2") (pintype "passive"))
      (node (ref "TP15") (pin "1") (pintype "passive"))
    )
    (net (code "24") (name "/MOTB") (class "Default")
      (node (ref "J3") (pin "2") (pinfunction "2_2") (pintype "passive"))
      (node (ref "NT4") (pin "2") (pinfunction "2_2") (pintype "passive"))
      (node (ref "Q1") (pin "1") (pinfunction "S_1") (pintype "passive"))
      (node (ref "Q1") (pin "2") (pinfunction "S_2") (pintype "passive"))
      (node (ref "Q1") (pin "3") (pinfunction "S_3") (pintype "passive"))
      (node (ref "Q6") (pin "5") (pinfunction "D_5") (pintype "passive"))
      (node (ref "Q6") (pin "6") (pinfunction "D_6") (pintype "passive"))
      (node (ref "Q6") (pin "7") (pinfunction "D_7") (pintype "passive"))
      (node (ref "Q6") (pin "8") (pinfunction "D_8") (pintype "passive"))
      (node (ref "Q6") (pin "9") (pinfunction "D_9") (pintype "passive"))
      (node (ref "R82") (pin "2") (pinfunction "2_2") (pintype "passive"))
      (node (ref "TP14") (pin "1") (pintype "passive"))
    )
    (net (code "25") (name "/MOTC") (class "Default")
      (node (ref "J3") (pin "3") (pinfunction "3_3") (pintype "passive"))
      (node (ref "NT7") (pin "2") (pinfunction "2_2") (pintype "passive"))
      (node (ref "Q2") (pin "1") (pinfunction "S_1") (pintype "passive"))
      (node (ref "Q2") (pin "2") (pinfunction "S_2") (pintype "passive"))
      (node (ref "Q2") (pin "3") (pinfunction "S_3") (pintype "passive"))
      (node (ref "Q4") (pin "5") (pinfunction "D_5") (pintype "passive"))
      (node (ref "Q4") (pin "6") (pinfunction "D_6") (pintype "passive"))
      (node (ref "Q4") (pin "7") (pinfunction "D_7") (pintype "passive"))
      (node (ref "Q4") (pin "8") (pinfunction "D_8") (pintype "passive"))
      (node (ref "Q4") (pin "9") (pinfunction "D_9") (pintype "passive"))
      (node (ref "R80") (pin "2") (pinfunction "2_2") (pintype "passive"))
      (node (ref "TP13") (pin "1") (pintype "passive"))
    )
    (net (code "26") (name "/POT") (class "Default")
      (node (ref "R5") (pin "2") (pinfunction "WIPER_2") (pintype "passive"))
    )
    (net (code "27") (name "/SCLK") (class "Default")
      (node (ref "R61") (pin "1") (pinfunction "1_1") (pintype "passive"))
    )
    (net (code "28") (name "/SDI") (class "Default")
      (node (ref "R64") (pin "1") (pinfunction "1_1") (pintype "passive"))
    )
    (net (code "29") (name "/SDO") (class "Default")
      (node (ref "R67") (pin "1") (pinfunction "1_1") (pintype "passive"))
    )
    (net (code "30") (name "/SHA") (class "Default")
      (node (ref "NT6") (pin "1") (pinfunction "1_1") (pintype "passive"))
      (node (ref "U9") (pin "6") (pinfunction "SHA_6") (pintype "input"))
    )
    (net (code "31") (name "/SHB") (class "Default")
      (node (ref "NT4") (pin "1") (pinfunction "1_1") (pintype "passive"))
      (node (ref "U9") (pin "11") (pinfunction "SHB_11") (pintype "input"))
    )
    (net (code "32") (name "/SHC") (class "Default")
      (node (ref "NT7") (pin "1") (pinfunction "1_1") (pintype "passive"))
      (node (ref "U9") (pin "14") (pinfunction "SHC_14") (pintype "input"))
    )
    (net (code "33") (name "/SLA") (class "Default")
      (node (ref "NT2") (pin "1") (pinfunction "1_1") (pintype "passive"))
      (node (ref "U9") (pin "8") (pinfunction "SLA_8") (pintype "input"))
    )
    (net (code "34") (name "/SLB") (class "Default")
      (node (ref "NT8") (pin "1") (pinfunction "1_1") (pintype "passive"))
      (node (ref "U9") (pin "9") (pinfunction "SLB_9") (pintype "input"))
    )
    (net (code "35") (name "/SLC") (class "Default")
      (node (ref "NT1") (pin "1") (pinfunction "1_1") (pintype "passive"))
      (node (ref "U9") (pin "16") (pinfunction "SLC_16") (pintype "input"))
    )
    (net (code "36") (name "/SN") (class "Default")
      (node (ref "NT3") (pin "2") (pinfunction "2_2") (pintype "passive"))
      (node (ref "R73") (pin "2") (pinfunction "2_2") (pintype "passive"))
    )
    (net (code "37") (name "/SP") (class "Default")
      (node (ref "NT9") (pin "2") (pinfunction "2_2") (pintype "passive"))
      (node (ref "U11") (pin "3") (pinfunction "IN+_3") (pintype "input"))
    )
    (net (code "38") (name "/VBUCK") (class "Default")
      (node (ref "R72") (pin "1") (pinfunction "1_1") (pintype "passive"))
    )
    (net (code "39") (name "/VDRAIN") (class "Default")
      (node (ref "C63") (pin "1") (pinfunction "1_1") (pintype "passive"))
      (node (ref "NT5") (pin "1") (pinfunction "1_1") (pintype "passive"))
      (node (ref "U9") (pin "3") (pinfunction "VDRAIN_3") (pintype "input"))
    )
    (net (code "40") (name "/VDS") (class "Default")
      (node (ref "R59") (pin "2") (pinfunction "2_2") (pintype "passive"))
      (node (ref "R60") (pin "1") (pinfunction "1_1") (pintype "passive"))
      (node (ref "R61") (pin "2") (pinfunction "2_2") (pintype "passive"))
      (node (ref "U9") (pin "20") (pinfunction "SCLK_20") (pintype "input"))
    )
    (net (code "41") (name "/VSENA") (class "Default")
      (node (ref "C74") (pin "1") (pinfunction "1_1") (pintype "passive"))
      (node (ref "R81") (pin "2") (pinfunction "2_2") (pintype "passive"))
      (node (ref "R83") (pin "1") (pinfunction "1_1") (pintype "passive"))
      (node (ref "U10") (pin "1") (pinfunction "D1+_1") (pintype "passive"))
    )
    (net (code "42") (name "/VSENB") (class "Default")
      (node (ref "C73") (pin "1") (pinfunction "1_1") (pintype "passive"))
      (node (ref "R79") (pin "2") (pinfunction "2_2") (pintype "passive"))
      (node (ref "R82") (pin "1") (pinfunction "1_1") (pintype "passive"))
      (node (ref "U10") (pin "2") (pinfunction "D1-_2") (pintype "passive"))
    )
    (net (code "43") (name "/VSENC") (class "Default")
      (node (ref "C72") (pin "1") (pinfunction "1_1") (pintype "passive"))
      (node (ref "R78") (pin "2") (pinfunction "2_2") (pintype "passive"))
      (node (ref "R80") (pin "1") (pinfunction "1_1") (pintype "passive"))
      (node (ref "U10") (pin "4") (pinfunction "D2+_4") (pintype "passive"))
    )
    (net (code "44") (name "/VSENVM") (class "Default")
      (node (ref "C68") (pin "1") (pinfunction "1_1") (pintype "passive"))
      (node (ref "R76") (pin "2") (pinfunction "2_2") (pintype "passive"))
      (node (ref "R77") (pin "1") (pinfunction "1_1") (pintype "passive"))
      (node (ref "U10") (pin "5") (pinfunction "D2-_5") (pintype "passive"))
    )
    (net (code "45") (name "/nFAULT") (class "Default")
      (node (ref "R70") (pin "1") (pinfunction "1_1") (pintype "passive"))
      (node (ref "R71") (pin "1") (pinfunction "1_1") (pintype "passive"))
      (node (ref "U9") (pin "17") (pinfunction "FAULT_17") (pintype "open_collector"))
    )
    (net (code "46") (name "/nSCS{slash}NC") (class "Default")
      (node (ref "U9") (pin "21") (pinfunction "SCS_21") (pintype "passive"))
    )
    (net (code "47") (name "3.3V") (class "Default")
      (node (ref "C66") (pin "1") (pinfunction "1_1") (pintype "passive"))
      (node (ref "D10") (pin "1") (pinfunction "A_1") (pintype "passive"))
      (node (ref "D8") (pin "1") (pinfunction "A_1") (pintype "passive"))
      (node (ref "J1") (pin "3") (pinfunction "3_3") (pintype "passive"))
      (node (ref "R42") (pin "2") (pinfunction "2_2") (pintype "passive"))
      (node (ref "R43") (pin "2") (pinfunction "2_2") (pintype "passive"))
      (node (ref "R45") (pin "2") (pinfunction "2_2") (pintype "passive"))
      (node (ref "R5") (pin "3") (pinfunction "CW_3") (pintype "passive"))
      (node (ref "R60") (pin "2") (pinfunction "2_2") (pintype "passive"))
      (node (ref "R63") (pin "2") (pinfunction "2_2") (pintype "passive"))
      (node (ref "R69") (pin "2") (pinfunction "2_2") (pintype "passive"))
      (node (ref "R70") (pin "2") (pinfunction "2_2") (pintype "passive"))
      (node (ref "U11") (pin "5") (pinfunction "V+_5") (pintype "power_in"))
    )
    (net (code "48") (name "5V") (class "Default")
      (node (ref "D7") (pin "1") (pinfunction "A_1") (pintype "passive"))
      (node (ref "J1") (pin "1") (pinfunction "1_1") (pintype "passive"))
    )
    (net (code "49") (name "GND") (class "Default")
      (node (ref "C29") (pin "2") (pinfunction "2_2") (pintype "passive"))
      (node (ref "C38") (pin "2") (pinfunction "2_2") (pintype "passive"))
      (node (ref "C40") (pin "2") (pinfunction "2_2") (pintype "passive"))
      (node (ref "C42") (pin "2") (pinfunction "2_2") (pintype "passive"))
      (node (ref "C54") (pin "2") (pinfunction "-_2") (pintype "passive"))
      (node (ref "C57") (pin "2") (pinfunction "2_2") (pintype "passive"))
      (node (ref "C58") (pin "2") (pinfunction "2_2") (pintype "passive"))
      (node (ref "C60") (pin "2") (pinfunction "2_2") (pintype "passive"))
      (node (ref "C61") (pin "2") (pinfunction "2_2") (pintype "passive"))
      (node (ref "C64") (pin "2") (pinfunction "-_2") (pintype "passive"))
      (node (ref "C66") (pin "2") (pinfunction "2_2") (pintype "passive"))
      (node (ref "C67") (pin "2") (pinfunction "2_2") (pintype "passive"))
      (node (ref "C68") (pin "2") (pinfunction "2_2") (pintype "passive"))
      (node (ref "C72") (pin "2") (pinfunction "2_2") (pintype "passive"))
      (node (ref "C73") (pin "2") (pinfunction "2_2") (pintype "passive"))
      (node (ref "C74") (pin "2") (pinfunction "2_2") (pintype "passive"))
      (node (ref "J2") (pin "5") (pinfunction "5_5") (pintype "passive"))
      (node (ref "J4") (pin "1") (pinfunction "1_1") (pintype "passive"))
      (node (ref "NT3") (pin "1") (pinfunction "1_1") (pintype "passive"))
      (node (ref "R33") (pin "1") (pinfunction "1_1") (pintype "passive"))
      (node (ref "R5") (pin "1") (pinfunction "CCW_1") (pintype "passive"))
      (node (ref "R53") (pin "1") (pinfunction "1_1") (pintype "passive"))
      (node (ref "R54") (pin "1") (pinfunction "1_1") (pintype "passive"))
      (node (ref "R59") (pin "1") (pinfunction "1_1") (pintype "passive"))
      (node (ref "R62") (pin "1") (pinfunction "1_1") (pintype "passive"))
      (node (ref "R65") (pin "1") (pinfunction "1_1") (pintype "passive"))
      (node (ref "R75") (pin "1") (pinfunction "1_1") (pintype "passive"))
      (node (ref "R76") (pin "1") (pinfunction "1_1") (pintype "passive"))
      (node (ref "R78") (pin "1") (pinfunction "1_1") (pintype "passive"))
      (node (ref "R79") (pin "1") (pinfunction "1_1") (pintype "passive"))
      (node (ref "R81") (pin "1") (pinfunction "1_1") (pintype "passive"))
      (node (ref "TP12") (pin "1") (pintype "passive"))
      (node (ref "TP3") (pin "1") (pinfunction "1_1") (pintype "passive"))
      (node (ref "TP3") (pin "2") (pinfunction "2_2") (pintype "passive"))
      (node (ref "TP4") (pin "1") (pinfunction "1_1") (pintype "passive"))
      (node (ref "TP4") (pin "2") (pinfunction "2_2") (pintype "passive"))
      (node (ref "U10") (pin "3") (pinfunction "GND_3") (pintype "power_in"))
      (node (ref "U10") (pin "8") (pinfunction "GND_8") (pintype "power_in"))
      (node (ref "U11") (pin "2") (pinfunction "V-_2") (pintype "power_in"))
      (node (ref "U9") (pin "30") (pinfunction "PGND_30") (pintype "power_in"))
      (node (ref "U9") (pin "33") (pinfunction "PAD_33") (pintype "power_in"))
    )
    (net (code "50") (name "Net-(C67-Pad1)") (class "Default")
      (node (ref "C67") (pin "1") (pinfunction "1_1") (pintype "passive"))
      (node (ref "C69") (pin "2") (pinfunction "2_2") (pintype "passive"))
      (node (ref "C70") (pin "2") (pinfunction "2_2") (pintype "passive"))
      (node (ref "C71") (pin "2") (pinfunction "2_2") (pintype "passive"))
      (node (ref "NT1") (pin "2") (pinfunction "2_2") (pintype "passive"))
      (node (ref "NT2") (pin "2") (pinfunction "2_2") (pintype "passive"))
      (node (ref "NT8") (pin "2") (pinfunction "2_2") (pintype "passive"))
      (node (ref "NT9") (pin "1") (pinfunction "1_1") (pintype "passive"))
      (node (ref "Q4") (pin "1") (pinfunction "S_1") (pintype "passive"))
      (node (ref "Q4") (pin "2") (pinfunction "S_2") (pintype "passive"))
      (node (ref "Q4") (pin "3") (pinfunction "S_3") (pintype "passive"))
      (node (ref "Q5") (pin "1") (pinfunction "S_1") (pintype "passive"))
      (node (ref "Q5") (pin "2") (pinfunction "S_2") (pintype "passive"))
      (node (ref "Q5") (pin "3") (pinfunction "S_3") (pintype "passive"))
      (node (ref "Q6") (pin "1") (pinfunction "S_1") (pintype "passive"))
      (node (ref "Q6") (pin "2") (pinfunction "S_2") (pintype "passive"))
      (node (ref "Q6") (pin "3") (pinfunction "S_3") (pintype "passive"))
      (node (ref "R75") (pin "2") (pinfunction "2_2") (pintype "passive"))
    )
    (net (code "51") (name "Net-(D3-K)") (class "Default")
      (node (ref "D3") (pin "2") (pinfunction "K_2") (pintype "passive"))
      (node (ref "R33") (pin "2") (pinfunction "2_2") (pintype "passive"))
    )
    (net (code "52") (name "Net-(D7-K)") (class "Default")
      (node (ref "D7") (pin "2") (pinfunction "K_2") (pintype "passive"))
      (node (ref "R53") (pin "2") (pinfunction "2_2") (pintype "passive"))
    )
    (net (code "53") (name "Net-(D8-K)") (class "Default")
      (node (ref "D8") (pin "2") (pinfunction "K_2") (pintype "passive"))
      (node (ref "R54") (pin "2") (pinfunction "2_2") (pintype "passive"))
    )
    (net (code "54") (name "Net-(D10-K)") (class "Default")
      (node (ref "D10") (pin "2") (pinfunction "K_2") (pintype "passive"))
      (node (ref "R71") (pin "2") (pinfunction "2_2") (pintype "passive"))
    )
    (net (code "55") (name "Net-(F1-Pad1)") (class "Default")
      (node (ref "F1") (pin "1") (pinfunction "1_1") (pintype "passive"))
      (node (ref "J4") (pin "2") (pinfunction "2_2") (pintype "passive"))
    )
    (net (code "56") (name "Net-(J1-Pad2)") (class "Default")
      (node (ref "J1") (pin "2") (pinfunction "2_2") (pintype "passive"))
      (node (ref "J2") (pin "1") (pinfunction "1_1") (pintype "passive"))
    )
    (net (code "57") (name "Net-(U9-CPH)") (class "Default")
      (node (ref "C59") (pin "1") (pinfunction "1_1") (pintype "passive"))
      (node (ref "U9") (pin "1") (pinfunction "CPH_1") (pintype "passive"))
    )
    (net (code "58") (name "Net-(U9-CPL)") (class "Default")
      (node (ref "C59") (pin "2") (pinfunction "2_2") (pintype "passive"))
      (node (ref "U9") (pin "32") (pinfunction "CPL_32") (pintype "passive"))
    )
    (net (code "59") (name "Net-(U9-SDO)") (class "Default")
      (node (ref "R65") (pin "2") (pinfunction "2_2") (pintype "passive"))
      (node (ref "R66") (pin "2") (pinfunction "2_2") (pintype "passive"))
      (node (ref "R67") (pin "2") (pinfunction "2_2") (pintype "passive"))
      (node (ref "R69") (pin "1") (pinfunction "1_1") (pintype "passive"))
      (node (ref "U9") (pin "18") (pinfunction "SDO_18") (pintype "passive"))
    )
    (net (code "60") (name "Net-(U9-VCP)") (class "Default")
      (node (ref "C63") (pin "2") (pinfunction "2_2") (pintype "passive"))
      (node (ref "U9") (pin "4") (pinfunction "VCP_4") (pintype "power_in"))
    )
    (net (code "61") (name "Net-(U9-VGLS)") (class "Default")
      (node (ref "C58") (pin "1") (pinfunction "1_1") (pintype "passive"))
      (node (ref "U9") (pin "31") (pinfunction "VGLS_31") (pintype "power_in"))
    )
    (net (code "62") (name "Net-(U11-IN-)") (class "Default")
      (node (ref "C65") (pin "2") (pinfunction "2_2") (pintype "passive"))
      (node (ref "R73") (pin "1") (pinfunction "1_1") (pintype "passive"))
      (node (ref "R74") (pin "2") (pinfunction "2_2") (pintype "passive"))
      (node (ref "U11") (pin "4") (pinfunction "IN-_4") (pintype "input"))
    )
    (net (code "63") (name "Net-(U11-OUT)") (class "Default")
      (node (ref "C65") (pin "1") (pinfunction "1_1") (pintype "passive"))
      (node (ref "R32") (pin "2") (pinfunction "2_2") (pintype "passive"))
      (node (ref "R74") (pin "1") (pinfunction "1_1") (pintype "passive"))
      (node (ref "U11") (pin "1") (pinfunction "OUT_1") (pintype "output"))
    )
    (net (code "64") (name "VM") (class "Default")
      (node (ref "C54") (pin "1") (pinfunction "+_1") (pintype "passive"))
      (node (ref "C64") (pin "1") (pinfunction "+_1") (pintype "passive"))
      (node (ref "C69") (pin "1") (pinfunction "1_1") (pintype "passive"))
      (node (ref "C70") (pin "1") (pinfunction "1_1") (pintype "passive"))
      (node (ref "C71") (pin "1") (pinfunction "1_1") (pintype "passive"))
      (node (ref "F1") (pin "2") (pinfunction "2_2") (pintype "passive"))
      (node (ref "NT5") (pin "2") (pinfunction "2_2") (pintype "passive"))
      (node (ref "Q1") (pin "5") (pinfunction "D_5") (pintype "passive"))
      (node (ref "Q1") (pin "6") (pinfunction "D_6") (pintype "passive"))
      (node (ref "Q1") (pin "7") (pinfunction "D_7") (pintype "passive"))
      (node (ref "Q1") (pin "8") (pinfunction "D_8") (pintype "passive"))
      (node (ref "Q1") (pin "9") (pinfunction "D_9") (pintype "passive"))
      (node (ref "Q2") (pin "5") (pinfunction "D_5") (pintype "passive"))
      (node (ref "Q2") (pin "6") (pinfunction "D_6") (pintype "passive"))
      (node (ref "Q2") (pin "7") (pinfunction "D_7") (pintype "passive"))
      (node (ref "Q2") (pin "8") (pinfunction "D_8") (pintype "passive"))
      (node (ref "Q2") (pin "9") (pinfunction "D_9") (pintype "passive"))
      (node (ref "Q3") (pin "5") (pinfunction "D_5") (pintype "passive"))
      (node (ref "Q3") (pin "6") (pinfunction "D_6") (pintype "passive"))
      (node (ref "Q3") (pin "7") (pinfunction "D_7") (pintype "passive"))
      (node (ref "Q3") (pin "8") (pinfunction "D_8") (pintype "passive"))
      (node (ref "Q3") (pin "9") (pinfunction "D_9") (pintype "passive"))
      (node (ref "R68") (pin "1") (pinfunction "1_1") (pintype "passive"))
      (node (ref "R77") (pin "2") (pinfunction "2_2") (pintype "passive"))
      (node (ref "TP9") (pin "1") (pintype "passive"))
    )
    (net (code "65") (name "unconnected-(U10-NC-Pad6)") (class "Default")
      (node (ref "U10") (pin "6") (pinfunction "NC_6") (pintype "passive+no_connect"))
    )
    (net (code "66") (name "unconnected-(U10-NC-Pad7)") (class "Default")
      (node (ref "U10") (pin "7") (pinfunction "NC_7") (pintype "passive+no_connect"))
    )
    (net (code "67") (name "unconnected-(U10-NC-Pad9)") (class "Default")
      (node (ref "U10") (pin "9") (pinfunction "NC_9") (pintype "passive+no_connect"))
    )
    (net (code "68") (name "unconnected-(U10-NC-Pad10)") (class "Default")
      (node (ref "U10") (pin "10") (pinfunction "NC_10") (pintype "passive+no_connect"))
    )
  )
)
